# PCF8583_1v3.net
KiCad netlist of a schematic drawn in EAGLE
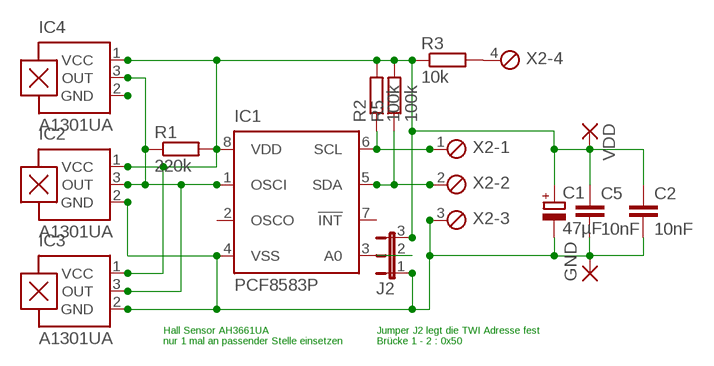
[diagram p0: schematic, sheet 1]

(export (version "E")
  (design (tool "Eeschema 10.0.6"))
  (components
    (comp (ref "C1")
      (value "47µF")
      (footprint "eagle-import:E2,5-5")
      (libsource (lib "eagle-import") (part "CPOL-EUE2.5-5"))
    )
    (comp (ref "C2")
      (value "10nF")
      (footprint "eagle-import:C025-024X044")
      (libsource (lib "eagle-import") (part "C-EU025-024X044"))
    )
    (comp (ref "C5")
      (value "10nF")
      (footprint "eagle-import:C025-024X044")
      (libsource (lib "eagle-import") (part "C-EU025-024X044"))
    )
    (comp (ref "GND")
      (value "2,54/1,0")
      (footprint "eagle-import:2,54_1,0")
      (libsource (lib "eagle-import") (part "2,54/1,0"))
    )
    (comp (ref "IC1")
      (value "PCF8583P")
      (footprint "eagle-import:DIL08")
      (libsource (lib "eagle-import") (part "PCF8583P"))
    )
    (comp (ref "IC2")
      (value "A1301UA")
      (footprint "eagle-import:SIP3-UA")
      (fields (field (name "MF") "ALLEGRO MICROSYSTEMS, INC.") (field (name "MPN") "A1301EUA-T"))
      (libsource (lib "eagle-import") (part "A13?UA01"))
    )
    (comp (ref "IC3")
      (value "A1301UA")
      (footprint "eagle-import:SIP3-UA")
      (fields (field (name "MF") "ALLEGRO MICROSYSTEMS, INC.") (field (name "MPN") "A1301EUA-T"))
      (libsource (lib "eagle-import") (part "A13?UA01"))
    )
    (comp (ref "IC4")
      (value "A1301UA")
      (footprint "eagle-import:SIP3-UA")
      (fields (field (name "MF") "ALLEGRO MICROSYSTEMS, INC.") (field (name "MPN") "A1301EUA-T"))
      (libsource (lib "eagle-import") (part "A13?UA01"))
    )
    (comp (ref "J2")
      (value "JP2E")
      (footprint "eagle-import:JP2")
      (libsource (lib "eagle-import") (part "JP2E"))
    )
    (comp (ref "R1")
      (value "220k")
      (footprint "eagle-import:0204_7")
      (libsource (lib "eagle-import") (part "R-EU_0204/7"))
    )
    (comp (ref "R2")
      (value "100k")
      (footprint "eagle-import:0204_7")
      (libsource (lib "eagle-import") (part "R-EU_0204/7"))
    )
    (comp (ref "R3")
      (value "10k")
      (footprint "eagle-import:0204_7")
      (libsource (lib "eagle-import") (part "R-EU_0204/7"))
    )
    (comp (ref "R5")
      (value "100k")
      (footprint "eagle-import:0204_7")
      (libsource (lib "eagle-import") (part "R-EU_0204/7"))
    )
    (comp (ref "VDD")
      (value "2,54/1,0")
      (footprint "eagle-import:2,54_1,0")
      (libsource (lib "eagle-import") (part "2,54/1,0"))
    )
    (comp (ref "X2")
      (value "MPT4")
      (footprint "eagle-import:4POL254")
      (libsource (lib "eagle-import") (part "MPT4"))
    )
  )
  (nets
    (net (code "1") (name "/GND") (class "Default")
      (node (ref "C1") (pin "-") (pinfunction "-_-") (pintype "passive"))
      (node (ref "C2") (pin "2") (pinfunction "2_2") (pintype "passive"))
      (node (ref "C5") (pin "2") (pinfunction "2_2") (pintype "passive"))
      (node (ref "GND") (pin "1") (pinfunction "P_1") (pintype "passive"))
      (node (ref "IC1") (pin "4") (pinfunction "VSS_4") (pintype "power_in"))
      (node (ref "IC2") (pin "2") (pinfunction "GND_2") (pintype "power_in"))
      (node (ref "IC3") (pin "2") (pinfunction "GND_2") (pintype "power_in"))
      (node (ref "IC4") (pin "2") (pinfunction "GND_2") (pintype "power_in"))
      (node (ref "J2") (pin "1") (pinfunction "1_1") (pintype "passive"))
      (node (ref "X2") (pin "3") (pinfunction "1_3") (pintype "passive"))
    )
    (net (code "2") (name "Net-(IC1-A0)") (class "Default")
      (node (ref "IC1") (pin "3") (pinfunction "A0_3") (pintype "input"))
      (node (ref "J2") (pin "2") (pinfunction "2_2") (pintype "passive"))
    )
    (net (code "3") (name "Net-(IC1-OSCI)") (class "Default")
      (node (ref "IC1") (pin "1") (pinfunction "OSCI_1") (pintype "input"))
      (node (ref "IC2") (pin "3") (pinfunction "OUT_3") (pintype "output"))
      (node (ref "IC3") (pin "3") (pinfunction "OUT_3") (pintype "output"))
      (node (ref "IC4") (pin "3") (pinfunction "OUT_3") (pintype "output"))
      (node (ref "R1") (pin "1") (pinfunction "1_1") (pintype "passive"))
    )
    (net (code "4") (name "Net-(IC1-SCL)") (class "Default")
      (node (ref "IC1") (pin "6") (pinfunction "SCL_6") (pintype "input"))
      (node (ref "R2") (pin "1") (pinfunction "1_1") (pintype "passive"))
      (node (ref "X2") (pin "1") (pinfunction "1_1") (pintype "passive"))
    )
    (net (code "5") (name "Net-(IC1-SDA)") (class "Default")
      (node (ref "IC1") (pin "5") (pinfunction "SDA_5") (pintype "bidirectional"))
      (node (ref "R5") (pin "1") (pinfunction "1_1") (pintype "passive"))
      (node (ref "X2") (pin "2") (pinfunction "1_2") (pintype "passive"))
    )
    (net (code "6") (name "Net-(IC1-VDD)") (class "Default")
      (node (ref "C1") (pin "+") (pinfunction "+_+") (pintype "passive"))
      (node (ref "C2") (pin "1") (pinfunction "1_1") (pintype "passive"))
      (node (ref "C5") (pin "1") (pinfunction "1_1") (pintype "passive"))
      (node (ref "IC1") (pin "8") (pinfunction "VDD_8") (pintype "power_in"))
      (node (ref "IC2") (pin "1") (pinfunction "VCC_1") (pintype "power_in"))
      (node (ref "IC3") (pin "1") (pinfunction "VCC_1") (pintype "power_in"))
      (node (ref "IC4") (pin "1") (pinfunction "VCC_1") (pintype "power_in"))
      (node (ref "J2") (pin "3") (pinfunction "3_3") (pintype "passive"))
      (node (ref "R1") (pin "2") (pinfunction "2_2") (pintype "passive"))
      (node (ref "R2") (pin "2") (pinfunction "2_2") (pintype "passive"))
      (node (ref "R3") (pin "1") (pinfunction "1_1") (pintype "passive"))
      (node (ref "R5") (pin "2") (pinfunction "2_2") (pintype "passive"))
      (node (ref "VDD") (pin "1") (pinfunction "P_1") (pintype "passive"))
    )
    (net (code "7") (name "Net-(X2D-1)") (class "Default")
      (node (ref "R3") (pin "2") (pinfunction "2_2") (pintype "passive"))
      (node (ref "X2") (pin "4") (pinfunction "1_4") (pintype "passive"))
    )
    (net (code "8") (name "unconnected-(IC1-OSCO-Pad2)") (class "Default")
      (node (ref "IC1") (pin "2") (pinfunction "OSCO_2") (pintype "output"))
    )
    (net (code "9") (name "unconnected-(IC1-~{INT}-Pad7)") (class "Default")
      (node (ref "IC1") (pin "7") (pinfunction "~{INT}_7") (pintype "open_collector"))
    )
  )
)
